# rtc_module.net
KiCad netlist of a schematic drawn in EAGLE
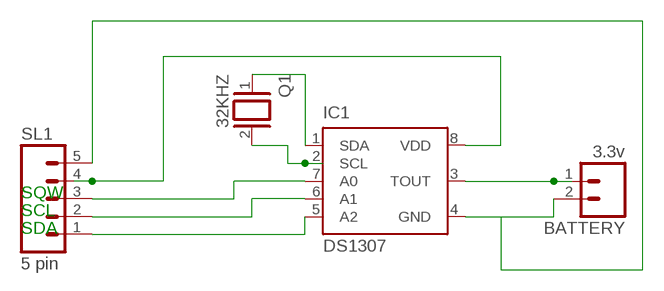
[diagram p0: schematic, sheet 1]

(export (version "E")
  (design (tool "Eeschema 10.0.6"))
  (components
    (comp (ref "BATTERY")
      (value "3.3v")
      (footprint "eagle-import:02P")
      (libsource (lib "eagle-import") (part "M02"))
    )
    (comp (ref "IC1")
      (value "DS1307")
      (footprint "eagle-import:DIL08")
      (fields (field (name "MPN") "DS1621"))
      (libsource (lib "eagle-import") (part "DS1621"))
    )
    (comp (ref "Q1")
      (value "32KHZ")
      (footprint "eagle-import:QS")
      (libsource (lib "eagle-import") (part "XTAL/S"))
    )
    (comp (ref "SL1")
      (value "5 pin")
      (footprint "eagle-import:05P")
      (libsource (lib "eagle-import") (part "M05"))
    )
  )
  (nets
    (net (code "1") (name "Net-(IC1-A0)") (class "Default")
      (node (ref "IC1") (pin "7") (pinfunction "A0_7") (pintype "input"))
      (node (ref "SL1") (pin "3") (pinfunction "3_3") (pintype "passive"))
    )
    (net (code "2") (name "Net-(IC1-A1)") (class "Default")
      (node (ref "IC1") (pin "6") (pinfunction "A1_6") (pintype "input"))
      (node (ref "SL1") (pin "2") (pinfunction "2_2") (pintype "passive"))
    )
    (net (code "3") (name "Net-(IC1-A2)") (class "Default")
      (node (ref "IC1") (pin "5") (pinfunction "A2_5") (pintype "input"))
      (node (ref "SL1") (pin "1") (pinfunction "1_1") (pintype "passive"))
    )
    (net (code "4") (name "Net-(IC1-GND)") (class "Default")
      (node (ref "BATTERY") (pin "2") (pinfunction "2_2") (pintype "passive"))
      (node (ref "IC1") (pin "4") (pinfunction "GND_4") (pintype "power_in"))
      (node (ref "SL1") (pin "5") (pinfunction "5_5") (pintype "passive"))
    )
    (net (code "5") (name "Net-(IC1-SCL)") (class "Default")
      (node (ref "IC1") (pin "2") (pinfunction "SCL_2") (pintype "input"))
      (node (ref "Q1") (pin "2") (pinfunction "2_2") (pintype "passive"))
    )
    (net (code "6") (name "Net-(IC1-SDA)") (class "Default")
      (node (ref "IC1") (pin "1") (pinfunction "SDA_1") (pintype "bidirectional"))
      (node (ref "Q1") (pin "1") (pinfunction "1_1") (pintype "passive"))
    )
    (net (code "7") (name "Net-(IC1-TOUT)") (class "Default")
      (node (ref "BATTERY") (pin "1") (pinfunction "1_1") (pintype "passive"))
      (node (ref "IC1") (pin "3") (pinfunction "TOUT_3") (pintype "output"))
    )
    (net (code "8") (name "Net-(IC1-VDD)") (class "Default")
      (node (ref "IC1") (pin "8") (pinfunction "VDD_8") (pintype "power_in"))
      (node (ref "SL1") (pin "4") (pinfunction "4_4") (pintype "passive"))
    )
  )
)
